# HDDA_encoder.net
KiCad netlist of a schematic drawn in Altium Designer
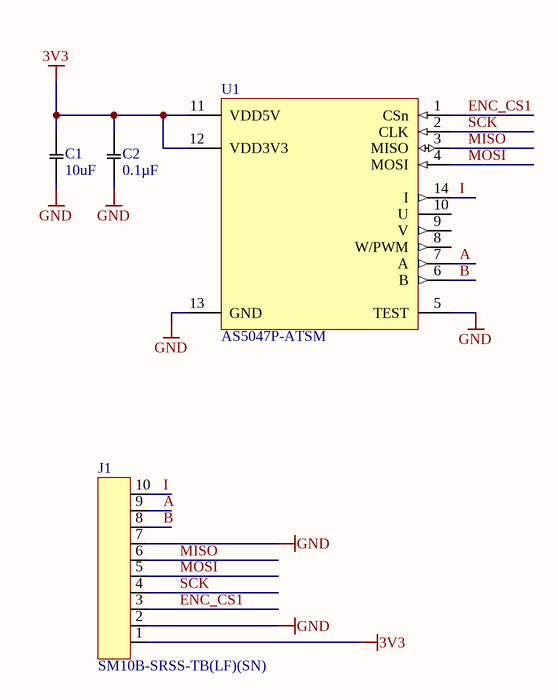
[diagram p0: HDDA_encoder.SchDoc]

(export (version "E")
  (design (tool "Eeschema 10.0.6"))
  (components
    (comp (ref "C1")
      (value "10uF")
      (footprint "C0603")
      (description "CAP CER 10UF 10V 10% X5R 0603")
      (fields
        (field (name "MANUFACTURER") "TDK Corporation")
        (field (name "MANUFACTURER PART NUMBER") "C1608X5R1A106K080AC")
      )
      (libsource (lib "capacitors") (part "C"))
    )
    (comp (ref "C2")
      (value "0.1µF")
      (footprint "C0402")
      (description "CAP CER 0.1UF 50V 10% X7R 0402")
      (fields
        (field (name "MANUFACTURER PART NUMBER") "C1005X7R1H104K050BB")
        (field (name "MANUFACTURER") "TDK Corporation")
      )
      (libsource (lib "capacitors") (part "C"))
    )
    (comp (ref "J1")
      (value "SM10B-SRSS-TB(LF)(SN)")
      (footprint "SM10B-SRSS-TB")
      (description "CONN HEADER SH 10POS SIDE 1MM TIN")
      (fields (field (name "MANUFACTURER") "JST Sales America Inc"))
      (libsource (lib "connectors_interconnects") (part "CONN_1_ROW_010_POS"))
    )
    (comp (ref "U1")
      (value "AS5047P-ATSM")
      (footprint "AS5047X")
      (description "IC ENCODER ROTARY 14TSSOP")
      (fields (field (name "MANUFACTURER") "ams"))
      (libsource (lib "sensors_transducers") (part "AS5047P"))
    )
  )
  (nets
    (net (code "1") (name "/A") (class "Default")
      (node (ref "J1") (pin "9") (pinfunction "9_9") (pintype "passive"))
      (node (ref "U1") (pin "7") (pinfunction "A_7") (pintype "output"))
    )
    (net (code "2") (name "/B") (class "Default")
      (node (ref "J1") (pin "8") (pinfunction "8_8") (pintype "passive"))
      (node (ref "U1") (pin "6") (pinfunction "B_6") (pintype "output"))
    )
    (net (code "3") (name "/ENC_CS1") (class "Default")
      (node (ref "J1") (pin "3") (pinfunction "3_3") (pintype "passive"))
      (node (ref "U1") (pin "1") (pinfunction "CSn_1") (pintype "input"))
    )
    (net (code "4") (name "/I") (class "Default")
      (node (ref "J1") (pin "10") (pinfunction "10_10") (pintype "passive"))
      (node (ref "U1") (pin "14") (pinfunction "I_14") (pintype "output"))
    )
    (net (code "5") (name "/MISO") (class "Default")
      (node (ref "J1") (pin "6") (pinfunction "6_6") (pintype "passive"))
      (node (ref "U1") (pin "3") (pinfunction "MISO_3") (pintype "bidirectional"))
    )
    (net (code "6") (name "/MOSI") (class "Default")
      (node (ref "J1") (pin "5") (pinfunction "5_5") (pintype "passive"))
      (node (ref "U1") (pin "4") (pinfunction "MOSI_4") (pintype "input"))
    )
    (net (code "7") (name "/SCK") (class "Default")
      (node (ref "J1") (pin "4") (pinfunction "4_4") (pintype "passive"))
      (node (ref "U1") (pin "2") (pinfunction "CLK_2") (pintype "input"))
    )
    (net (code "8") (name "3V3") (class "Default")
      (node (ref "C1") (pin "1") (pinfunction "1_1") (pintype "passive"))
      (node (ref "C2") (pin "1") (pinfunction "1_1") (pintype "passive"))
      (node (ref "J1") (pin "1") (pinfunction "1_1") (pintype "passive"))
      (node (ref "U1") (pin "11") (pinfunction "VDD5V_11") (pintype "power_in"))
      (node (ref "U1") (pin "12") (pinfunction "VDD3V3_12") (pintype "power_in"))
    )
    (net (code "9") (name "GND") (class "Default")
      (node (ref "C1") (pin "2") (pinfunction "2_2") (pintype "passive"))
      (node (ref "C2") (pin "2") (pinfunction "2_2") (pintype "passive"))
      (node (ref "J1") (pin "2") (pinfunction "2_2") (pintype "passive"))
      (node (ref "J1") (pin "7") (pinfunction "7_7") (pintype "passive"))
      (node (ref "U1") (pin "13") (pinfunction "GND_13") (pintype "power_in"))
      (node (ref "U1") (pin "5") (pinfunction "TEST_5") (pintype "passive"))
    )
    (net (code "10") (name "unconnected-(U1-U-Pad10)") (class "Default")
      (node (ref "U1") (pin "10") (pinfunction "U_10") (pintype "passive"))
    )
    (net (code "11") (name "unconnected-(U1-V-Pad9)") (class "Default")
      (node (ref "U1") (pin "9") (pinfunction "V_9") (pintype "output"))
    )
    (net (code "12") (name "unconnected-(U1-W{slash}PWM-Pad8)") (class "Default")
      (node (ref "U1") (pin "8") (pinfunction "W/PWM_8") (pintype "output"))
    )
  )
)
